# MM_board.net
KiCad netlist of a schematic drawn in EAGLE
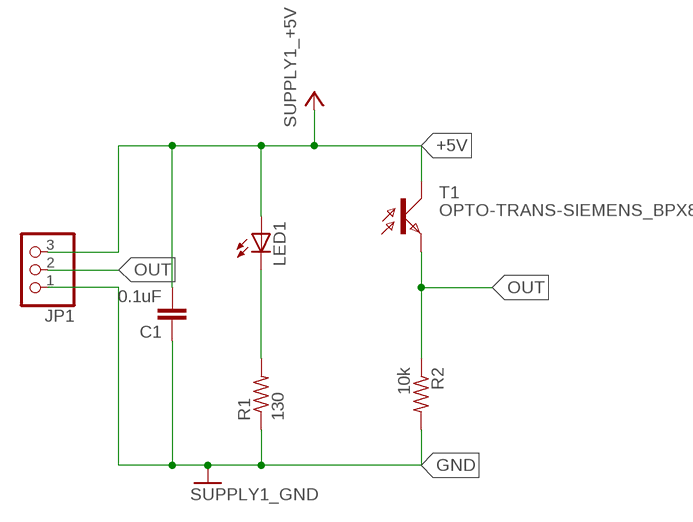
[diagram p0: schematic, sheet 1]

(export (version "E")
  (design (tool "Eeschema 10.0.6"))
  (components
    (comp (ref "C1")
      (value "0.1uF")
      (footprint "eagle-import:RCL_C1206")
      (libsource (lib "eagle-import") (part "RCL_C-EUC1206"))
    )
    (comp (ref "JP1")
      (value "PINHEAD_PINHD-1X3")
      (footprint "eagle-import:PINHEAD_1X03")
      (libsource (lib "eagle-import") (part "PINHEAD_PINHD-1X3"))
    )
    (comp (ref "LED1")
      (value "LED_LED5MM")
      (footprint "eagle-import:LED_LED5MM")
      (libsource (lib "eagle-import") (part "LED_LED5MM"))
    )
    (comp (ref "R1")
      (value "130")
      (footprint "eagle-import:RCL_R1206")
      (libsource (lib "eagle-import") (part "RCL_R-US_R1206"))
    )
    (comp (ref "R2")
      (value "10k")
      (footprint "eagle-import:RCL_R1206")
      (libsource (lib "eagle-import") (part "RCL_R-US_R1206"))
    )
    (comp (ref "T1")
      (value "OPTO-TRANS-SIEMENS_BPX81")
      (footprint "eagle-import:OPTO-TRANS-SIEMENS_BPX81")
      (libsource (lib "eagle-import") (part "OPTO-TRANS-SIEMENS_BPX81"))
    )
  )
  (nets
    (net (code "1") (name "+5V") (class "Default")
      (node (ref "C1") (pin "2") (pinfunction "2_2") (pintype "passive"))
      (node (ref "JP1") (pin "3") (pinfunction "3_3") (pintype "passive"))
      (node (ref "LED1") (pin "A") (pinfunction "A_A") (pintype "passive"))
      (node (ref "T1") (pin "C") (pinfunction "C_C") (pintype "passive"))
    )
    (net (code "2") (name "GND") (class "Default")
      (node (ref "C1") (pin "1") (pinfunction "1_1") (pintype "passive"))
      (node (ref "JP1") (pin "1") (pinfunction "1_1") (pintype "passive"))
      (node (ref "R1") (pin "1") (pinfunction "1_1") (pintype "passive"))
      (node (ref "R2") (pin "2") (pinfunction "2_2") (pintype "passive"))
    )
    (net (code "3") (name "Net-(LED1-C)") (class "Default")
      (node (ref "LED1") (pin "K") (pinfunction "C_K") (pintype "passive"))
      (node (ref "R1") (pin "2") (pinfunction "2_2") (pintype "passive"))
    )
    (net (code "4") (name "OUT") (class "Default")
      (node (ref "JP1") (pin "2") (pinfunction "2_2") (pintype "passive"))
      (node (ref "R2") (pin "1") (pinfunction "1_1") (pintype "passive"))
      (node (ref "T1") (pin "E") (pinfunction "E_E") (pintype "passive"))
    )
  )
)
